# CD74HC4067_MUX_2.net
KiCad netlist of a schematic drawn in Altium Designer
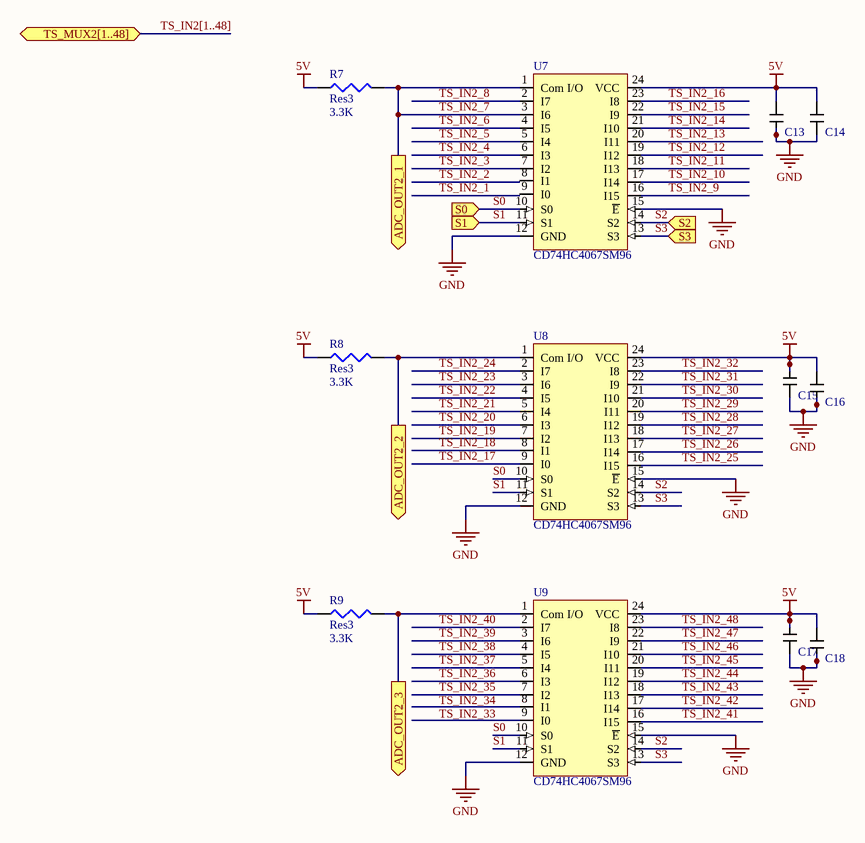
[diagram p0: CD74HC4067_MUX_2.SchDoc]

(export (version "E")
  (design (tool "Eeschema 10.0.6"))
  (components
    (comp (ref "C13")
      (value "0.1uF Cap")
      (footprint "CAPC1608X09M")
      (description "C0603C101K8GAC7867 Kemet Capacitor")
      (libsource (lib "0.1_uF_Kemet_Cap") (part "0.1uF Cap"))
    )
    (comp (ref "C14")
      (value "1uF Samsung Cap")
      (footprint "CAPC1608X09M")
      (libsource (lib "1uF_Samsung_Cap") (part "1uF Samsung Cap"))
    )
    (comp (ref "C15")
      (value "0.1uF Cap")
      (footprint "CAPC1608X09M")
      (description "C0603C101K8GAC7867 Kemet Capacitor")
      (libsource (lib "0.1_uF_Kemet_Cap") (part "0.1uF Cap"))
    )
    (comp (ref "C16")
      (value "1uF Samsung Cap")
      (footprint "CAPC1608X09M")
      (libsource (lib "1uF_Samsung_Cap") (part "1uF Samsung Cap"))
    )
    (comp (ref "C17")
      (value "0.1uF Cap")
      (footprint "CAPC1608X09M")
      (description "C0603C101K8GAC7867 Kemet Capacitor")
      (libsource (lib "0.1_uF_Kemet_Cap") (part "0.1uF Cap"))
    )
    (comp (ref "C18")
      (value "1uF Samsung Cap")
      (footprint "CAPC1608X09M")
      (libsource (lib "1uF_Samsung_Cap") (part "1uF Samsung Cap"))
    )
    (comp (ref "R7")
      (value "Res3")
      (footprint "J1-0603")
      (description "Resistor")
      (fields (field (name "ALTIUM_VALUE") "3.3K") (field (name "PUBLISHER") "Altium Limited"))
      (libsource (lib "Miscellaneous Devices") (part "Res3"))
    )
    (comp (ref "R8")
      (value "Res3")
      (footprint "J1-0603")
      (description "Resistor")
      (fields (field (name "ALTIUM_VALUE") "3.3K") (field (name "PUBLISHER") "Altium Limited"))
      (libsource (lib "Miscellaneous Devices") (part "Res3"))
    )
    (comp (ref "R9")
      (value "Res3")
      (footprint "J1-0603")
      (description "Resistor")
      (fields (field (name "ALTIUM_VALUE") "3.3K") (field (name "PUBLISHER") "Altium Limited"))
      (libsource (lib "Miscellaneous Devices") (part "Res3"))
    )
    (comp (ref "U7")
      (value "CD74HC4067SM96")
      (footprint "SOIC-24_MUX")
      (libsource (lib "TI_Mux") (part "CD74HC4067SM96"))
    )
    (comp (ref "U8")
      (value "CD74HC4067SM96")
      (footprint "SOIC-24_MUX")
      (libsource (lib "TI_Mux") (part "CD74HC4067SM96"))
    )
    (comp (ref "U9")
      (value "CD74HC4067SM96")
      (footprint "SOIC-24_MUX")
      (libsource (lib "TI_Mux") (part "CD74HC4067SM96"))
    )
  )
  (nets
    (net (code "49") (name "/ADC_OUT2_2") (class "Default")
      (node (ref "R8") (pin "2") (pinfunction "2_2") (pintype "passive"))
      (node (ref "U8") (pin "1") (pinfunction "Com_I/O_1") (pintype "bidirectional"))
    )
    (net (code "50") (name "/ADC_OUT2_3") (class "Default")
      (node (ref "R9") (pin "2") (pinfunction "2_2") (pintype "passive"))
      (node (ref "U9") (pin "1") (pinfunction "Com_I/O_1") (pintype "bidirectional"))
    )
    (net (code "51") (name "/S0") (class "Default")
      (node (ref "U7") (pin "10") (pinfunction "S0_10") (pintype "input"))
      (node (ref "U8") (pin "10") (pinfunction "S0_10") (pintype "input"))
      (node (ref "U9") (pin "10") (pinfunction "S0_10") (pintype "input"))
    )
    (net (code "52") (name "/S1") (class "Default")
      (node (ref "U7") (pin "11") (pinfunction "S1_11") (pintype "input"))
      (node (ref "U8") (pin "11") (pinfunction "S1_11") (pintype "input"))
      (node (ref "U9") (pin "11") (pinfunction "S1_11") (pintype "input"))
    )
    (net (code "53") (name "/S2") (class "Default")
      (node (ref "U7") (pin "14") (pinfunction "S2_14") (pintype "input"))
      (node (ref "U8") (pin "14") (pinfunction "S2_14") (pintype "input"))
      (node (ref "U9") (pin "14") (pinfunction "S2_14") (pintype "input"))
    )
    (net (code "54") (name "/S3") (class "Default")
      (node (ref "U7") (pin "13") (pinfunction "S3_13") (pintype "input"))
      (node (ref "U8") (pin "13") (pinfunction "S3_13") (pintype "input"))
      (node (ref "U9") (pin "13") (pinfunction "S3_13") (pintype "input"))
    )
    (net (code "58") (name "/TS_IN2_3") (class "Default")
      (node (ref "U7") (pin "7") (pinfunction "I2_7") (pintype "passive"))
    )
    (net (code "59") (name "/TS_IN2_4") (class "Default")
      (node (ref "U7") (pin "6") (pinfunction "I3_6") (pintype "passive"))
    )
    (net (code "60") (name "/TS_IN2_5") (class "Default")
      (node (ref "U7") (pin "5") (pinfunction "I4_5") (pintype "passive"))
    )
    (net (code "61") (name "/TS_IN2_6") (class "Default")
      (node (ref "U7") (pin "4") (pinfunction "I5_4") (pintype "passive"))
    )
    (net (code "62") (name "/TS_IN2_7") (class "Default")
      (node (ref "R7") (pin "2") (pinfunction "2_2") (pintype "passive"))
      (node (ref "U7") (pin "1") (pinfunction "Com_I/O_1") (pintype "bidirectional"))
      (node (ref "U7") (pin "3") (pinfunction "I6_3") (pintype "passive"))
    )
    (net (code "63") (name "/TS_IN2_8") (class "Default")
      (node (ref "U7") (pin "2") (pinfunction "I7_2") (pintype "passive"))
    )
    (net (code "64") (name "/TS_IN2_9") (class "Default")
      (node (ref "U7") (pin "16") (pinfunction "I15_16") (pintype "passive"))
    )
    (net (code "65") (name "/TS_IN2_10") (class "Default")
      (node (ref "U7") (pin "17") (pinfunction "I14_17") (pintype "passive"))
    )
    (net (code "66") (name "/TS_IN2_11") (class "Default")
      (node (ref "U7") (pin "18") (pinfunction "I13_18") (pintype "passive"))
    )
    (net (code "67") (name "/TS_IN2_12") (class "Default")
      (node (ref "U7") (pin "19") (pinfunction "I12_19") (pintype "passive"))
    )
    (net (code "68") (name "/TS_IN2_13") (class "Default")
      (node (ref "U7") (pin "20") (pinfunction "I11_20") (pintype "passive"))
    )
    (net (code "69") (name "/TS_IN2_14") (class "Default")
      (node (ref "U7") (pin "21") (pinfunction "I10_21") (pintype "passive"))
    )
    (net (code "70") (name "/TS_IN2_15") (class "Default")
      (node (ref "U7") (pin "22") (pinfunction "I9_22") (pintype "passive"))
    )
    (net (code "71") (name "/TS_IN2_16") (class "Default")
      (node (ref "U7") (pin "23") (pinfunction "I8_23") (pintype "passive"))
    )
    (net (code "72") (name "/TS_IN2_17") (class "Default")
      (node (ref "U8") (pin "9") (pinfunction "I0_9") (pintype "passive"))
    )
    (net (code "73") (name "/TS_IN2_18") (class "Default")
      (node (ref "U8") (pin "8") (pinfunction "I1_8") (pintype "passive"))
    )
    (net (code "74") (name "/TS_IN2_19") (class "Default")
      (node (ref "U8") (pin "7") (pinfunction "I2_7") (pintype "passive"))
    )
    (net (code "75") (name "/TS_IN2_20") (class "Default")
      (node (ref "U8") (pin "6") (pinfunction "I3_6") (pintype "passive"))
    )
    (net (code "76") (name "/TS_IN2_21") (class "Default")
      (node (ref "U8") (pin "5") (pinfunction "I4_5") (pintype "passive"))
    )
    (net (code "77") (name "/TS_IN2_22") (class "Default")
      (node (ref "U8") (pin "4") (pinfunction "I5_4") (pintype "passive"))
    )
    (net (code "78") (name "/TS_IN2_23") (class "Default")
      (node (ref "U8") (pin "3") (pinfunction "I6_3") (pintype "passive"))
    )
    (net (code "79") (name "/TS_IN2_24") (class "Default")
      (node (ref "U8") (pin "2") (pinfunction "I7_2") (pintype "passive"))
    )
    (net (code "80") (name "/TS_IN2_25") (class "Default")
      (node (ref "U8") (pin "16") (pinfunction "I15_16") (pintype "passive"))
    )
    (net (code "81") (name "/TS_IN2_26") (class "Default")
      (node (ref "U8") (pin "17") (pinfunction "I14_17") (pintype "passive"))
    )
    (net (code "82") (name "/TS_IN2_27") (class "Default")
      (node (ref "U8") (pin "18") (pinfunction "I13_18") (pintype "passive"))
    )
    (net (code "83") (name "/TS_IN2_28") (class "Default")
      (node (ref "U8") (pin "19") (pinfunction "I12_19") (pintype "passive"))
    )
    (net (code "84") (name "/TS_IN2_29") (class "Default")
      (node (ref "U8") (pin "20") (pinfunction "I11_20") (pintype "passive"))
    )
    (net (code "85") (name "/TS_IN2_30") (class "Default")
      (node (ref "U8") (pin "21") (pinfunction "I10_21") (pintype "passive"))
    )
    (net (code "86") (name "/TS_IN2_31") (class "Default")
      (node (ref "U8") (pin "22") (pinfunction "I9_22") (pintype "passive"))
    )
    (net (code "87") (name "/TS_IN2_32") (class "Default")
      (node (ref "U8") (pin "23") (pinfunction "I8_23") (pintype "passive"))
    )
    (net (code "90") (name "/TS_IN2_35") (class "Default")
      (node (ref "U9") (pin "7") (pinfunction "I2_7") (pintype "passive"))
    )
    (net (code "91") (name "/TS_IN2_36") (class "Default")
      (node (ref "U9") (pin "6") (pinfunction "I3_6") (pintype "passive"))
    )
    (net (code "92") (name "/TS_IN2_37") (class "Default")
      (node (ref "U9") (pin "5") (pinfunction "I4_5") (pintype "passive"))
    )
    (net (code "93") (name "/TS_IN2_38") (class "Default")
      (node (ref "U9") (pin "4") (pinfunction "I5_4") (pintype "passive"))
    )
    (net (code "94") (name "/TS_IN2_39") (class "Default")
      (node (ref "U9") (pin "3") (pinfunction "I6_3") (pintype "passive"))
    )
    (net (code "95") (name "/TS_IN2_40") (class "Default")
      (node (ref "U9") (pin "2") (pinfunction "I7_2") (pintype "passive"))
    )
    (net (code "96") (name "/TS_IN2_41") (class "Default")
      (node (ref "U9") (pin "16") (pinfunction "I15_16") (pintype "passive"))
    )
    (net (code "97") (name "/TS_IN2_42") (class "Default")
      (node (ref "U9") (pin "17") (pinfunction "I14_17") (pintype "passive"))
    )
    (net (code "98") (name "/TS_IN2_43") (class "Default")
      (node (ref "U9") (pin "18") (pinfunction "I13_18") (pintype "passive"))
    )
    (net (code "99") (name "/TS_IN2_44") (class "Default")
      (node (ref "U9") (pin "19") (pinfunction "I12_19") (pintype "passive"))
    )
    (net (code "100") (name "/TS_IN2_45") (class "Default")
      (node (ref "U9") (pin "20") (pinfunction "I11_20") (pintype "passive"))
    )
    (net (code "101") (name "/TS_IN2_46") (class "Default")
      (node (ref "U9") (pin "21") (pinfunction "I10_21") (pintype "passive"))
    )
    (net (code "102") (name "/TS_IN2_47") (class "Default")
      (node (ref "U9") (pin "22") (pinfunction "I9_22") (pintype "passive"))
    )
    (net (code "103") (name "/TS_IN2_48") (class "Default")
      (node (ref "U9") (pin "23") (pinfunction "I8_23") (pintype "passive"))
    )
    (net (code "104") (name "5V") (class "Default")
      (node (ref "C13") (pin "2") (pinfunction "2_2") (pintype "passive"))
      (node (ref "C14") (pin "2") (pinfunction "2_2") (pintype "passive"))
      (node (ref "C15") (pin "2") (pinfunction "2_2") (pintype "passive"))
      (node (ref "C16") (pin "2") (pinfunction "2_2") (pintype "passive"))
      (node (ref "C17") (pin "2") (pinfunction "2_2") (pintype "passive"))
      (node (ref "C18") (pin "2") (pinfunction "2_2") (pintype "passive"))
      (node (ref "R7") (pin "1") (pinfunction "1_1") (pintype "passive"))
      (node (ref "R8") (pin "1") (pinfunction "1_1") (pintype "passive"))
      (node (ref "R9") (pin "1") (pinfunction "1_1") (pintype "passive"))
      (node (ref "U7") (pin "24") (pinfunction "VCC_24") (pintype "power_in"))
      (node (ref "U8") (pin "24") (pinfunction "VCC_24") (pintype "power_in"))
      (node (ref "U9") (pin "24") (pinfunction "VCC_24") (pintype "power_in"))
    )
    (net (code "105") (name "GND") (class "Default")
      (node (ref "C13") (pin "1") (pinfunction "1_1") (pintype "passive"))
      (node (ref "C14") (pin "1") (pinfunction "1_1") (pintype "passive"))
      (node (ref "C15") (pin "1") (pinfunction "1_1") (pintype "passive"))
      (node (ref "C16") (pin "1") (pinfunction "1_1") (pintype "passive"))
      (node (ref "C17") (pin "1") (pinfunction "1_1") (pintype "passive"))
      (node (ref "C18") (pin "1") (pinfunction "1_1") (pintype "passive"))
      (node (ref "U7") (pin "12") (pinfunction "GND_12") (pintype "power_in"))
      (node (ref "U7") (pin "15") (pinfunction "~{E}_15") (pintype "input"))
      (node (ref "U8") (pin "12") (pinfunction "GND_12") (pintype "power_in"))
      (node (ref "U8") (pin "15") (pinfunction "~{E}_15") (pintype "input"))
      (node (ref "U9") (pin "12") (pinfunction "GND_12") (pintype "power_in"))
      (node (ref "U9") (pin "15") (pinfunction "~{E}_15") (pintype "input"))
    )
    (net (code "106") (name "unconnected-(U7-I0-Pad9)") (class "Default")
      (node (ref "U7") (pin "9") (pinfunction "I0_9") (pintype "passive"))
    )
    (net (code "107") (name "unconnected-(U7-I1-Pad8)") (class "Default")
      (node (ref "U7") (pin "8") (pinfunction "I1_8") (pintype "passive"))
    )
    (net (code "108") (name "unconnected-(U9-I0-Pad9)") (class "Default")
      (node (ref "U9") (pin "9") (pinfunction "I0_9") (pintype "passive"))
    )
    (net (code "109") (name "unconnected-(U9-I1-Pad8)") (class "Default")
      (node (ref "U9") (pin "8") (pinfunction "I1_8") (pintype "passive"))
    )
  )
)
